# soth-core.net
KiCad netlist of a schematic drawn in EAGLE
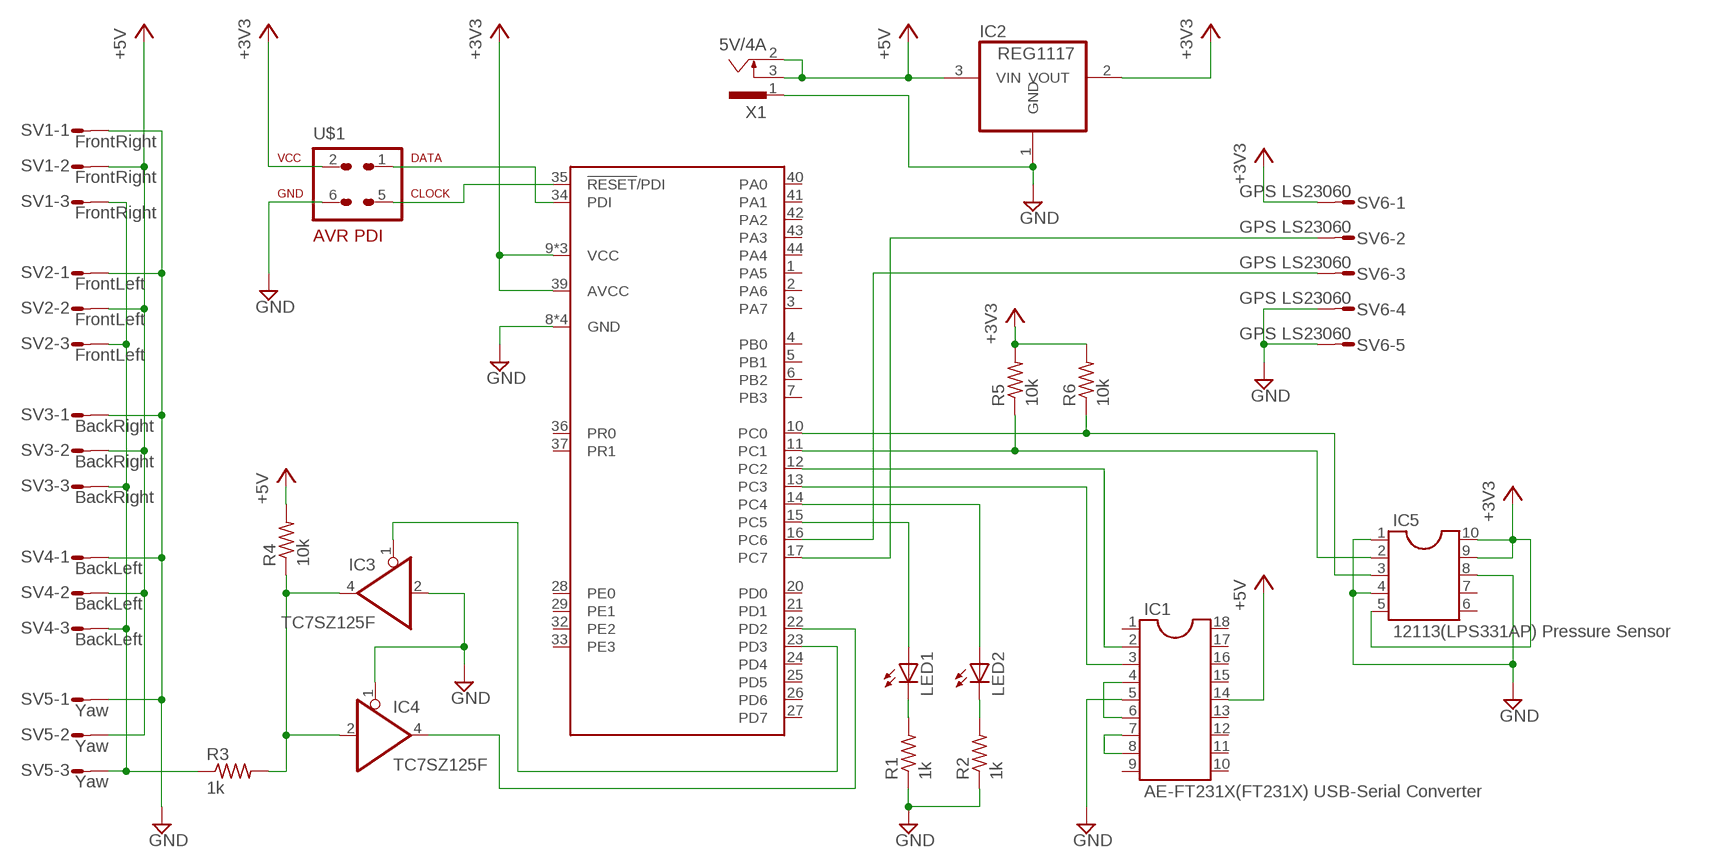
[diagram p0: schematic, sheet 1]

(export (version "E")
  (design (tool "Eeschema 10.0.6"))
  (components
    (comp (ref "IC1")
      (value "AE-FT231X(FT231X) USB-Serial Converter")
      (footprint "eagle-import:SOCKET-18")
      (libsource (lib "eagle-import") (part "DIL18S"))
    )
    (comp (ref "IC2")
      (value "REG1117")
      (footprint "eagle-import:SOT223")
      (libsource (lib "eagle-import") (part "REG1117"))
    )
    (comp (ref "IC3")
      (value "TC7SZ125F")
      (footprint "eagle-import:SOT23-5")
      (libsource (lib "eagle-import") (part "741G125DBVAHC"))
    )
    (comp (ref "IC4")
      (value "TC7SZ125F")
      (footprint "eagle-import:SOT23-5")
      (libsource (lib "eagle-import") (part "741G125DBVAHC"))
    )
    (comp (ref "IC5")
      (value "12113(LPS331AP) Pressure Sensor")
      (footprint "eagle-import:DIL10")
      (libsource (lib "eagle-import") (part "DIL10"))
    )
    (comp (ref "LED1")
      (value "LED")
      (footprint "eagle-import:SMARTLED-TTW")
      (libsource (lib "eagle-import") (part "LED"))
    )
    (comp (ref "LED2")
      (value "LED")
      (footprint "eagle-import:SMARTLED-TTW")
      (libsource (lib "eagle-import") (part "LED"))
    )
    (comp (ref "R1")
      (value "1k")
      (footprint "eagle-import:R0805")
      (libsource (lib "eagle-import") (part "R-US_R0805"))
    )
    (comp (ref "R2")
      (value "1k")
      (footprint "eagle-import:R0805")
      (libsource (lib "eagle-import") (part "R-US_R0805"))
    )
    (comp (ref "R3")
      (value "1k")
      (footprint "eagle-import:R0805")
      (libsource (lib "eagle-import") (part "R-US_R0805"))
    )
    (comp (ref "R4")
      (value "10k")
      (footprint "eagle-import:R0805")
      (libsource (lib "eagle-import") (part "R-US_R0805"))
    )
    (comp (ref "R5")
      (value "10k")
      (footprint "eagle-import:R0805")
      (libsource (lib "eagle-import") (part "R-US_R0805"))
    )
    (comp (ref "R6")
      (value "10k")
      (footprint "eagle-import:R0805")
      (libsource (lib "eagle-import") (part "R-US_R0805"))
    )
    (comp (ref "SV1")
      (value "FrontRight")
      (footprint "eagle-import:S03P")
      (libsource (lib "eagle-import") (part "S03P"))
    )
    (comp (ref "SV2")
      (value "FrontLeft")
      (footprint "eagle-import:S03P")
      (libsource (lib "eagle-import") (part "S03P"))
    )
    (comp (ref "SV3")
      (value "BackRight")
      (footprint "eagle-import:S03P")
      (libsource (lib "eagle-import") (part "S03P"))
    )
    (comp (ref "SV4")
      (value "BackLeft")
      (footprint "eagle-import:S03P")
      (libsource (lib "eagle-import") (part "S03P"))
    )
    (comp (ref "SV5")
      (value "Yaw")
      (footprint "eagle-import:S03P")
      (libsource (lib "eagle-import") (part "S03P"))
    )
    (comp (ref "SV6")
      (value "GPS LS23060")
      (footprint "eagle-import:S05P")
      (libsource (lib "eagle-import") (part "S05P"))
    )
    (comp (ref "U$1")
      (value "AVR-PDIVERT")
      (footprint "eagle-import:AVR-ISP-6")
      (libsource (lib "eagle-import") (part "AVR-PDIVERT"))
    )
    (comp (ref "U1")
      (value "ATXMEGA32D4-AU")
      (footprint "eagle-import:TQFP-44A-44")
      (libsource (lib "eagle-import") (part "ATXMEGA32D4-AU"))
    )
    (comp (ref "X1")
      (value "5V/4A")
      (footprint "eagle-import:733980-62")
      (libsource (lib "eagle-import") (part "73398?0-62"))
    )
  )
  (nets
    (net (code "1") (name "+3V3") (class "Default")
      (node (ref "IC2") (pin "2") (pinfunction "VOUT_2") (pintype "output"))
      (node (ref "IC5") (pin "10") (pinfunction "10_10") (pintype "passive"))
      (node (ref "IC5") (pin "5") (pinfunction "5_5") (pintype "passive"))
      (node (ref "IC5") (pin "9") (pinfunction "9_9") (pintype "passive"))
      (node (ref "R5") (pin "2") (pinfunction "2_2") (pintype "passive"))
      (node (ref "R6") (pin "2") (pinfunction "2_2") (pintype "passive"))
      (node (ref "SV6") (pin "1") (pinfunction "S_1") (pintype "passive"))
      (node (ref "U$1") (pin "2") (pinfunction "2_2") (pintype "passive"))
      (node (ref "U1") (pin "19") (pinfunction "VCC_19") (pintype "power_in"))
      (node (ref "U1") (pin "31") (pinfunction "VCC_31") (pintype "power_in"))
      (node (ref "U1") (pin "39") (pinfunction "AVCC_39") (pintype "power_in"))
      (node (ref "U1") (pin "9") (pinfunction "VCC_9") (pintype "power_in"))
    )
    (net (code "2") (name "+5V") (class "Default")
      (node (ref "IC1") (pin "14") (pinfunction "14_14") (pintype "passive"))
      (node (ref "IC2") (pin "3") (pinfunction "VIN_3") (pintype "input"))
      (node (ref "R4") (pin "2") (pinfunction "2_2") (pintype "passive"))
      (node (ref "SV1") (pin "2") (pinfunction "S_2") (pintype "passive"))
      (node (ref "SV2") (pin "2") (pinfunction "S_2") (pintype "passive"))
      (node (ref "SV3") (pin "2") (pinfunction "S_2") (pintype "passive"))
      (node (ref "SV4") (pin "2") (pinfunction "S_2") (pintype "passive"))
      (node (ref "SV5") (pin "2") (pinfunction "S_2") (pintype "passive"))
      (node (ref "X1") (pin "2") (pinfunction "2_2") (pintype "passive"))
      (node (ref "X1") (pin "3") (pinfunction "3_3") (pintype "passive"))
    )
    (net (code "3") (name "GND") (class "Default")
      (node (ref "IC1") (pin "5") (pinfunction "5_5") (pintype "passive"))
      (node (ref "IC2") (pin "1") (pinfunction "GND_1") (pintype "power_in"))
      (node (ref "IC3") (pin "2") (pinfunction "I_2") (pintype "input"))
      (node (ref "IC4") (pin "1") (pinfunction "OE_1") (pintype "input"))
      (node (ref "IC5") (pin "1") (pinfunction "1_1") (pintype "passive"))
      (node (ref "IC5") (pin "4") (pinfunction "4_4") (pintype "passive"))
      (node (ref "IC5") (pin "8") (pinfunction "8_8") (pintype "passive"))
      (node (ref "R1") (pin "1") (pinfunction "1_1") (pintype "passive"))
      (node (ref "R2") (pin "1") (pinfunction "1_1") (pintype "passive"))
      (node (ref "SV1") (pin "1") (pinfunction "S_1") (pintype "passive"))
      (node (ref "SV2") (pin "1") (pinfunction "S_1") (pintype "passive"))
      (node (ref "SV3") (pin "1") (pinfunction "S_1") (pintype "passive"))
      (node (ref "SV4") (pin "1") (pinfunction "S_1") (pintype "passive"))
      (node (ref "SV5") (pin "1") (pinfunction "S_1") (pintype "passive"))
      (node (ref "SV6") (pin "4") (pinfunction "S_4") (pintype "passive"))
      (node (ref "SV6") (pin "5") (pinfunction "S_5") (pintype "passive"))
      (node (ref "U$1") (pin "6") (pinfunction "6_6") (pintype "passive"))
      (node (ref "U1") (pin "18") (pinfunction "GND_18") (pintype "power_in"))
      (node (ref "U1") (pin "30") (pinfunction "GND_30") (pintype "power_in"))
      (node (ref "U1") (pin "38") (pinfunction "GND_38") (pintype "power_in"))
      (node (ref "U1") (pin "8") (pinfunction "GND_8") (pintype "power_in"))
      (node (ref "X1") (pin "1") (pinfunction "1_1") (pintype "passive"))
    )
    (net (code "4") (name "Net-(IC1-Pad4)") (class "Default")
      (node (ref "IC1") (pin "4") (pinfunction "4_4") (pintype "passive"))
      (node (ref "IC1") (pin "6") (pinfunction "6_6") (pintype "passive"))
    )
    (net (code "5") (name "Net-(IC1-Pad7)") (class "Default")
      (node (ref "IC1") (pin "7") (pinfunction "7_7") (pintype "passive"))
      (node (ref "IC1") (pin "8") (pinfunction "8_8") (pintype "passive"))
    )
    (net (code "6") (name "Net-(IC3A-O)") (class "Default")
      (node (ref "IC3") (pin "4") (pinfunction "O_4") (pintype "tri_state"))
      (node (ref "IC4") (pin "2") (pinfunction "I_2") (pintype "input"))
      (node (ref "R3") (pin "2") (pinfunction "2_2") (pintype "passive"))
      (node (ref "R4") (pin "1") (pinfunction "1_1") (pintype "passive"))
    )
    (net (code "7") (name "Net-(IC3A-OE)") (class "Default")
      (node (ref "IC3") (pin "1") (pinfunction "OE_1") (pintype "input"))
      (node (ref "U1") (pin "23") (pinfunction "PD3_23") (pintype "bidirectional"))
    )
    (net (code "8") (name "Net-(IC4A-O)") (class "Default")
      (node (ref "IC4") (pin "4") (pinfunction "O_4") (pintype "tri_state"))
      (node (ref "U1") (pin "22") (pinfunction "PD2_22") (pintype "bidirectional"))
    )
    (net (code "9") (name "Net-(LED1-A)") (class "Default")
      (node (ref "LED1") (pin "A@1") (pinfunction "A_A@1") (pintype "passive"))
      (node (ref "U1") (pin "15") (pinfunction "PC5_15") (pintype "bidirectional"))
    )
    (net (code "10") (name "Net-(LED1-C)") (class "Default")
      (node (ref "LED1") (pin "C@1") (pinfunction "C_C@1") (pintype "passive"))
      (node (ref "R1") (pin "2") (pinfunction "2_2") (pintype "passive"))
    )
    (net (code "11") (name "Net-(LED2-A)") (class "Default")
      (node (ref "LED2") (pin "A@1") (pinfunction "A_A@1") (pintype "passive"))
      (node (ref "U1") (pin "14") (pinfunction "PC4_14") (pintype "bidirectional"))
    )
    (net (code "12") (name "Net-(LED2-C)") (class "Default")
      (node (ref "LED2") (pin "C@1") (pinfunction "C_C@1") (pintype "passive"))
      (node (ref "R2") (pin "2") (pinfunction "2_2") (pintype "passive"))
    )
    (net (code "13") (name "Net-(SV1C-S)") (class "Default")
      (node (ref "R3") (pin "1") (pinfunction "1_1") (pintype "passive"))
      (node (ref "SV1") (pin "3") (pinfunction "S_3") (pintype "passive"))
      (node (ref "SV2") (pin "3") (pinfunction "S_3") (pintype "passive"))
      (node (ref "SV3") (pin "3") (pinfunction "S_3") (pintype "passive"))
      (node (ref "SV4") (pin "3") (pinfunction "S_3") (pintype "passive"))
      (node (ref "SV5") (pin "3") (pinfunction "S_3") (pintype "passive"))
    )
    (net (code "14") (name "Net-(SV6B-S)") (class "Default")
      (node (ref "SV6") (pin "2") (pinfunction "S_2") (pintype "passive"))
      (node (ref "U1") (pin "17") (pinfunction "PC7_17") (pintype "bidirectional"))
    )
    (net (code "15") (name "Net-(SV6C-S)") (class "Default")
      (node (ref "SV6") (pin "3") (pinfunction "S_3") (pintype "passive"))
      (node (ref "U1") (pin "16") (pinfunction "PC6_16") (pintype "bidirectional"))
    )
    (net (code "16") (name "Net-(U1-PC0)") (class "Default")
      (node (ref "IC5") (pin "3") (pinfunction "3_3") (pintype "passive"))
      (node (ref "R6") (pin "1") (pinfunction "1_1") (pintype "passive"))
      (node (ref "U1") (pin "10") (pinfunction "PC0_10") (pintype "bidirectional"))
    )
    (net (code "17") (name "Net-(U1-PC1)") (class "Default")
      (node (ref "IC5") (pin "2") (pinfunction "2_2") (pintype "passive"))
      (node (ref "R5") (pin "1") (pinfunction "1_1") (pintype "passive"))
      (node (ref "U1") (pin "11") (pinfunction "PC1_11") (pintype "bidirectional"))
    )
    (net (code "18") (name "Net-(U1-PC2)") (class "Default")
      (node (ref "IC1") (pin "2") (pinfunction "2_2") (pintype "passive"))
      (node (ref "U1") (pin "12") (pinfunction "PC2_12") (pintype "bidirectional"))
    )
    (net (code "19") (name "Net-(U1-PC3)") (class "Default")
      (node (ref "IC1") (pin "3") (pinfunction "3_3") (pintype "passive"))
      (node (ref "U1") (pin "13") (pinfunction "PC3_13") (pintype "bidirectional"))
    )
    (net (code "20") (name "Net-(U1-PDI)") (class "Default")
      (node (ref "U$1") (pin "1") (pinfunction "1_1") (pintype "passive"))
      (node (ref "U1") (pin "34") (pinfunction "PDI_34") (pintype "bidirectional"))
    )
    (net (code "21") (name "Net-(U1-~{RESET}{slash}PDI)") (class "Default")
      (node (ref "U$1") (pin "5") (pinfunction "5_5") (pintype "passive"))
      (node (ref "U1") (pin "35") (pinfunction "~{RESET}/PDI_35") (pintype "bidirectional"))
    )
    (net (code "22") (name "unconnected-(IC1-Pad1)") (class "Default")
      (node (ref "IC1") (pin "1") (pinfunction "1_1") (pintype "passive"))
    )
    (net (code "23") (name "unconnected-(IC1-Pad9)") (class "Default")
      (node (ref "IC1") (pin "9") (pinfunction "9_9") (pintype "passive"))
    )
    (net (code "24") (name "unconnected-(IC1-Pad10)") (class "Default")
      (node (ref "IC1") (pin "10") (pinfunction "10_10") (pintype "passive"))
    )
    (net (code "25") (name "unconnected-(IC1-Pad11)") (class "Default")
      (node (ref "IC1") (pin "11") (pinfunction "11_11") (pintype "passive"))
    )
    (net (code "26") (name "unconnected-(IC1-Pad12)") (class "Default")
      (node (ref "IC1") (pin "12") (pinfunction "12_12") (pintype "passive"))
    )
    (net (code "27") (name "unconnected-(IC1-Pad13)") (class "Default")
      (node (ref "IC1") (pin "13") (pinfunction "13_13") (pintype "passive"))
    )
    (net (code "28") (name "unconnected-(IC1-Pad15)") (class "Default")
      (node (ref "IC1") (pin "15") (pinfunction "15_15") (pintype "passive"))
    )
    (net (code "29") (name "unconnected-(IC1-Pad16)") (class "Default")
      (node (ref "IC1") (pin "16") (pinfunction "16_16") (pintype "passive"))
    )
    (net (code "30") (name "unconnected-(IC1-Pad17)") (class "Default")
      (node (ref "IC1") (pin "17") (pinfunction "17_17") (pintype "passive"))
    )
    (net (code "31") (name "unconnected-(IC1-Pad18)") (class "Default")
      (node (ref "IC1") (pin "18") (pinfunction "18_18") (pintype "passive"))
    )
    (net (code "32") (name "unconnected-(IC5-Pad6)") (class "Default")
      (node (ref "IC5") (pin "6") (pinfunction "6_6") (pintype "passive"))
    )
    (net (code "33") (name "unconnected-(IC5-Pad7)") (class "Default")
      (node (ref "IC5") (pin "7") (pinfunction "7_7") (pintype "passive"))
    )
    (net (code "34") (name "unconnected-(U1-PA0-Pad40)") (class "Default")
      (node (ref "U1") (pin "40") (pinfunction "PA0_40") (pintype "bidirectional"))
    )
    (net (code "35") (name "unconnected-(U1-PA1-Pad41)") (class "Default")
      (node (ref "U1") (pin "41") (pinfunction "PA1_41") (pintype "bidirectional"))
    )
    (net (code "36") (name "unconnected-(U1-PA2-Pad42)") (class "Default")
      (node (ref "U1") (pin "42") (pinfunction "PA2_42") (pintype "bidirectional"))
    )
    (net (code "37") (name "unconnected-(U1-PA3-Pad43)") (class "Default")
      (node (ref "U1") (pin "43") (pinfunction "PA3_43") (pintype "bidirectional"))
    )
    (net (code "38") (name "unconnected-(U1-PA4-Pad44)") (class "Default")
      (node (ref "U1") (pin "44") (pinfunction "PA4_44") (pintype "bidirectional"))
    )
    (net (code "39") (name "unconnected-(U1-PA5-Pad1)") (class "Default")
      (node (ref "U1") (pin "1") (pinfunction "PA5_1") (pintype "bidirectional"))
    )
    (net (code "40") (name "unconnected-(U1-PA6-Pad2)") (class "Default")
      (node (ref "U1") (pin "2") (pinfunction "PA6_2") (pintype "bidirectional"))
    )
    (net (code "41") (name "unconnected-(U1-PA7-Pad3)") (class "Default")
      (node (ref "U1") (pin "3") (pinfunction "PA7_3") (pintype "bidirectional"))
    )
    (net (code "42") (name "unconnected-(U1-PB0-Pad4)") (class "Default")
      (node (ref "U1") (pin "4") (pinfunction "PB0_4") (pintype "bidirectional"))
    )
    (net (code "43") (name "unconnected-(U1-PB1-Pad5)") (class "Default")
      (node (ref "U1") (pin "5") (pinfunction "PB1_5") (pintype "bidirectional"))
    )
    (net (code "44") (name "unconnected-(U1-PB2-Pad6)") (class "Default")
      (node (ref "U1") (pin "6") (pinfunction "PB2_6") (pintype "bidirectional"))
    )
    (net (code "45") (name "unconnected-(U1-PB3-Pad7)") (class "Default")
      (node (ref "U1") (pin "7") (pinfunction "PB3_7") (pintype "bidirectional"))
    )
    (net (code "46") (name "unconnected-(U1-PD0-Pad20)") (class "Default")
      (node (ref "U1") (pin "20") (pinfunction "PD0_20") (pintype "bidirectional"))
    )
    (net (code "47") (name "unconnected-(U1-PD1-Pad21)") (class "Default")
      (node (ref "U1") (pin "21") (pinfunction "PD1_21") (pintype "bidirectional"))
    )
    (net (code "48") (name "unconnected-(U1-PD4-Pad24)") (class "Default")
      (node (ref "U1") (pin "24") (pinfunction "PD4_24") (pintype "bidirectional"))
    )
    (net (code "49") (name "unconnected-(U1-PD5-Pad25)") (class "Default")
      (node (ref "U1") (pin "25") (pinfunction "PD5_25") (pintype "bidirectional"))
    )
    (net (code "50") (name "unconnected-(U1-PD6-Pad26)") (class "Default")
      (node (ref "U1") (pin "26") (pinfunction "PD6_26") (pintype "bidirectional"))
    )
    (net (code "51") (name "unconnected-(U1-PD7-Pad27)") (class "Default")
      (node (ref "U1") (pin "27") (pinfunction "PD7_27") (pintype "bidirectional"))
    )
    (net (code "52") (name "unconnected-(U1-PE0-Pad28)") (class "Default")
      (node (ref "U1") (pin "28") (pinfunction "PE0_28") (pintype "bidirectional"))
    )
    (net (code "53") (name "unconnected-(U1-PE1-Pad29)") (class "Default")
      (node (ref "U1") (pin "29") (pinfunction "PE1_29") (pintype "bidirectional"))
    )
    (net (code "54") (name "unconnected-(U1-PE2-Pad32)") (class "Default")
      (node (ref "U1") (pin "32") (pinfunction "PE2_32") (pintype "bidirectional"))
    )
    (net (code "55") (name "unconnected-(U1-PE3-Pad33)") (class "Default")
      (node (ref "U1") (pin "33") (pinfunction "PE3_33") (pintype "bidirectional"))
    )
    (net (code "56") (name "unconnected-(U1-PR0-Pad36)") (class "Default")
      (node (ref "U1") (pin "36") (pinfunction "PR0_36") (pintype "bidirectional"))
    )
    (net (code "57") (name "unconnected-(U1-PR1-Pad37)") (class "Default")
      (node (ref "U1") (pin "37") (pinfunction "PR1_37") (pintype "bidirectional"))
    )
  )
)
